# EtherCAT.net
KiCad netlist of a schematic drawn in Altium Designer
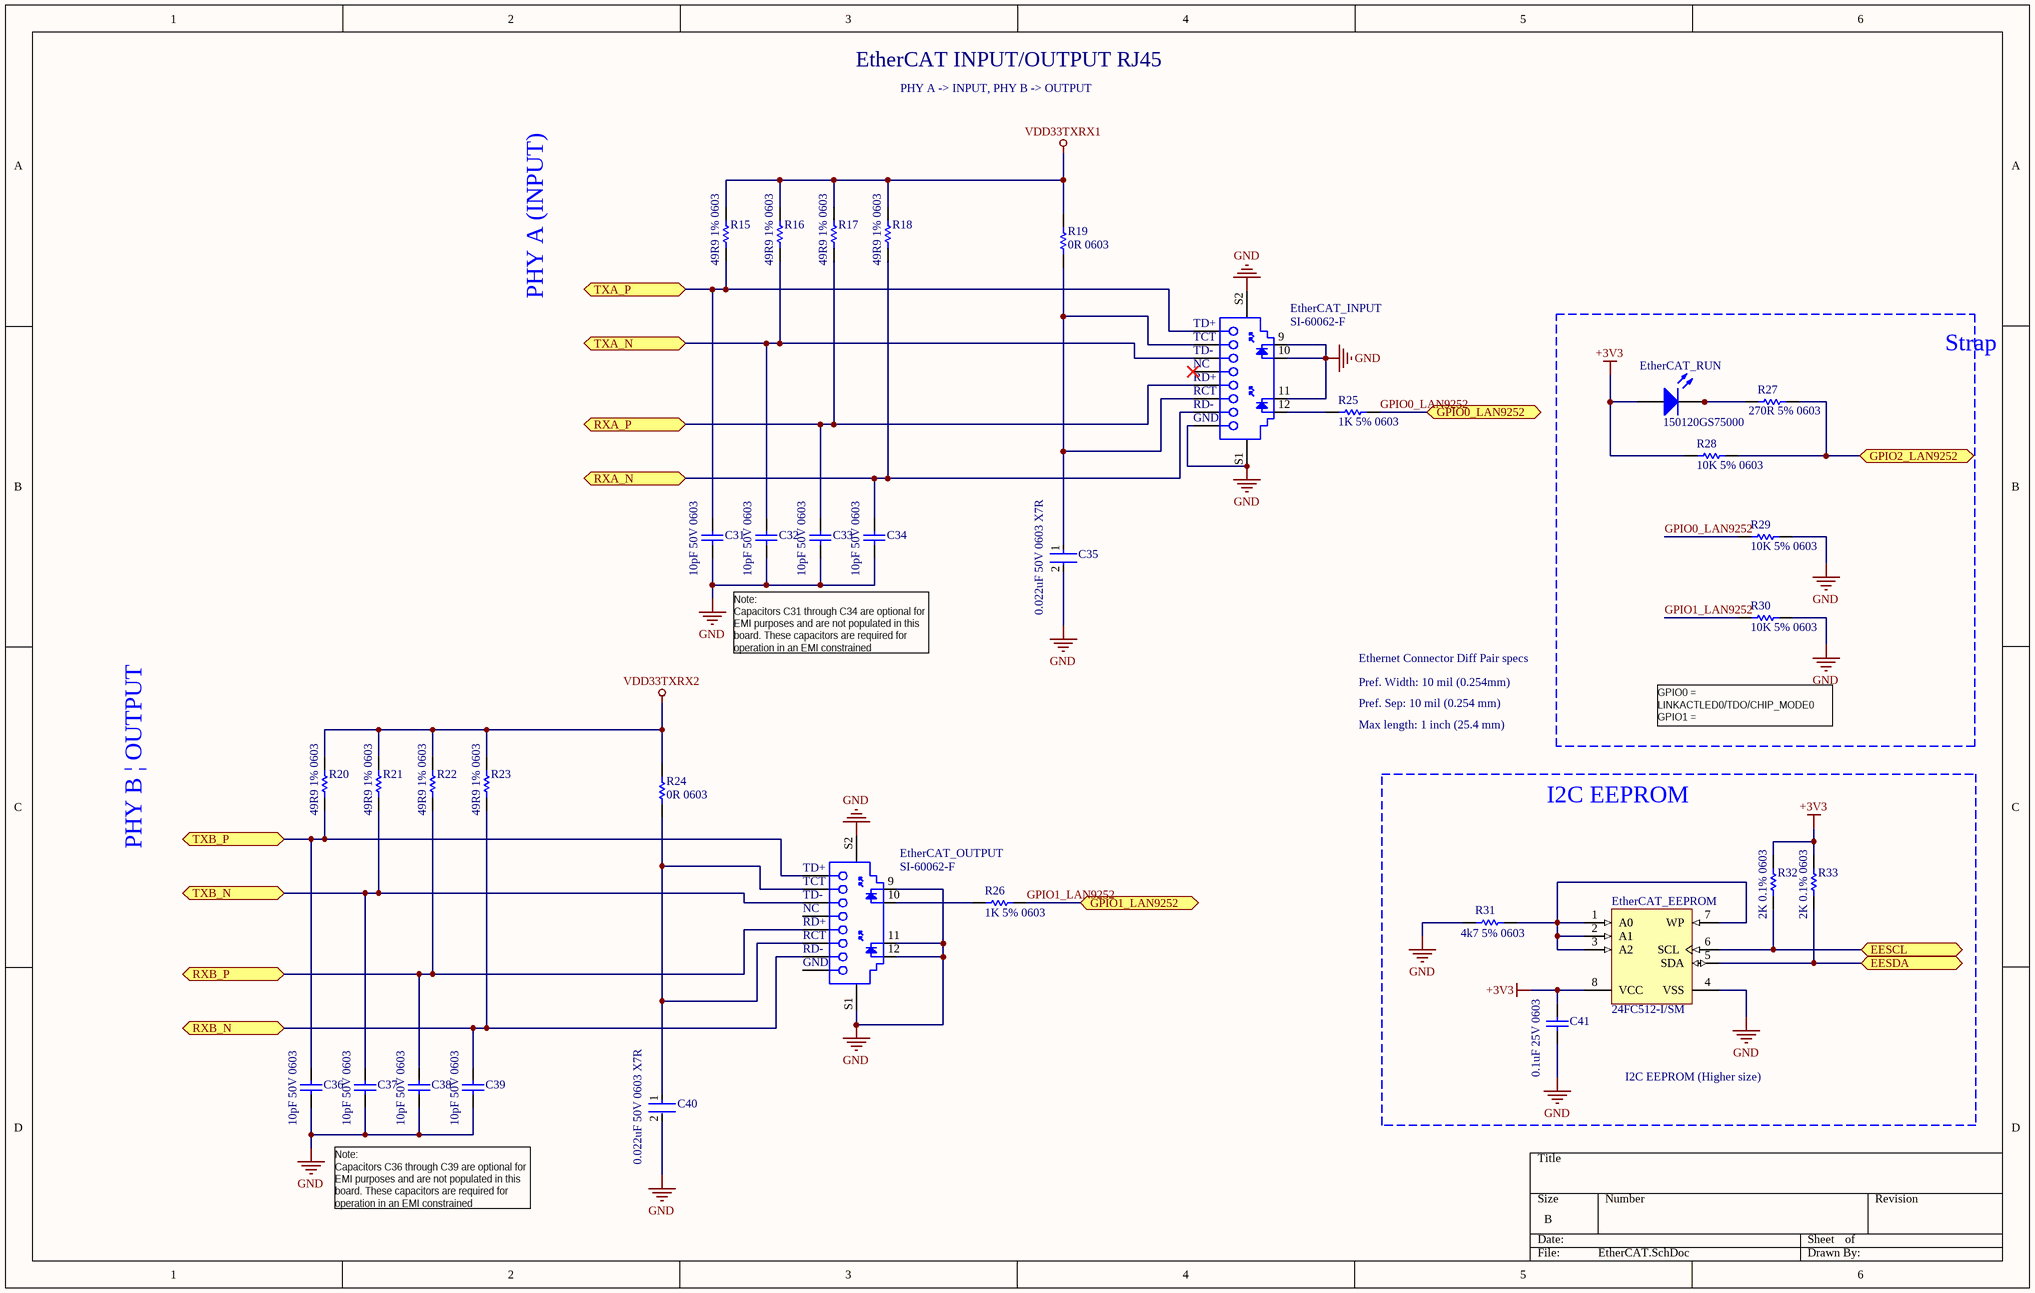
[diagram p0: EtherCAT.SchDoc]

(export (version "E")
  (design (tool "Eeschema 10.0.6"))
  (components
    (comp (ref "C31")
      (value "10pF 50V 0603")
      (footprint "CAPC1608X90X35LL10T15")
      (fields (field (name "PART NUMBER") "GRM1885C1H100JA01D") (field (name "MANUFACTURER") "Murata"))
      (libsource (lib "Altium Content Vault") (part "CAP"))
    )
    (comp (ref "C32")
      (value "10pF 50V 0603")
      (footprint "CAPC1608X90X35LL10T15")
      (fields (field (name "PART NUMBER") "GRM1885C1H100JA01D") (field (name "MANUFACTURER") "Murata"))
      (libsource (lib "Altium Content Vault") (part "CAP"))
    )
    (comp (ref "C33")
      (value "10pF 50V 0603")
      (footprint "CAPC1608X90X35LL10T15")
      (fields (field (name "PART NUMBER") "GRM1885C1H100JA01D") (field (name "MANUFACTURER") "Murata"))
      (libsource (lib "Altium Content Vault") (part "CAP"))
    )
    (comp (ref "C34")
      (value "10pF 50V 0603")
      (footprint "CAPC1608X90X35LL10T15")
      (fields (field (name "PART NUMBER") "GRM1885C1H100JA01D") (field (name "MANUFACTURER") "Murata"))
      (libsource (lib "Altium Content Vault") (part "CAP"))
    )
    (comp (ref "C35")
      (value "0.022uF 50V 0603 X7R")
      (footprint "FP-C0603C-CF-MFG")
      (description "Ceramic Capacitor 0.022Uf 50V, X7R, 10%, 0603, Full Reel")
      (fields
        (field (name "OCTOPART") "https://octopart.com/c0603c223k5ractu-kemet-97352")
        (field (name "MANUFACTURER PART NUMBER") "C0603C223K5RACTU")
      )
      (libsource (lib "Altium Content Vault") (part "b4654b650e69147ec39a6b967a45e02"))
    )
    (comp (ref "C36")
      (value "10pF 50V 0603")
      (footprint "CAPC1608X90X35LL10T15")
      (fields (field (name "PART NUMBER") "GRM1885C1H100JA01D") (field (name "MANUFACTURER") "Murata"))
      (libsource (lib "Altium Content Vault") (part "CAP"))
    )
    (comp (ref "C37")
      (value "10pF 50V 0603")
      (footprint "CAPC1608X90X35LL10T15")
      (fields (field (name "PART NUMBER") "GRM1885C1H100JA01D") (field (name "MANUFACTURER") "Murata"))
      (libsource (lib "Altium Content Vault") (part "CAP"))
    )
    (comp (ref "C38")
      (value "10pF 50V 0603")
      (footprint "CAPC1608X90X35LL10T15")
      (fields (field (name "PART NUMBER") "GRM1885C1H100JA01D") (field (name "MANUFACTURER") "Murata"))
      (libsource (lib "Altium Content Vault") (part "CAP"))
    )
    (comp (ref "C39")
      (value "10pF 50V 0603")
      (footprint "CAPC1608X90X35LL10T15")
      (fields (field (name "PART NUMBER") "GRM1885C1H100JA01D") (field (name "MANUFACTURER") "Murata"))
      (libsource (lib "Altium Content Vault") (part "CAP"))
    )
    (comp (ref "C40")
      (value "0.022uF 50V 0603 X7R")
      (footprint "FP-C0603C-CF-MFG")
      (description "Ceramic Capacitor 0.022Uf 50V, X7R, 10%, 0603, Full Reel")
      (fields
        (field (name "OCTOPART") "https://octopart.com/c0603c223k5ractu-kemet-97352")
        (field (name "MANUFACTURER PART NUMBER") "C0603C223K5RACTU")
      )
      (libsource (lib "Altium Content Vault") (part "b4654b650e69147ec39a6b967a45e02"))
    )
    (comp (ref "C41")
      (value "0.1uF 25V 0603")
      (footprint "CAPC1608X90X35LL10T15")
      (fields (field (name "PART NUMBER") "GRM188R71E104KA01D") (field (name "MANUFACTURER") "Murata"))
      (libsource (lib "Altium Content Vault") (part "CAP"))
    )
    (comp (ref "EtherCAT_EEPROM")
      (value "24FC512-I/SM")
      (footprint "SOIJ-SM8_M")
      (description "512Kbit, 1MHz, 2.5V, I2C Serial EEPROM, 8-Pin SOIC 208mil, Industrial Temperature")
      (libsource (lib "Altium Content Vault") (part "MEM-SEEPROM-34AA02-IL8"))
    )
    (comp (ref "EtherCAT_INPUT")
      (value "SI-60062-F")
      (footprint "BELF-SI-60062-F_V")
      (description "1 Port RJ45 Magjack Connector with Yellow and Green LED, 10/100 Base-T, 12-Pin THD, RoHS, Tray")
      (fields (field (name "MANUFACTURER") "Bel Fuse"))
      (libsource (lib "Altium Content Vault") (part "RJ45-12-2SHLD"))
    )
    (comp (ref "EtherCAT_OUTPUT")
      (value "SI-60062-F")
      (footprint "BELF-SI-60062-F_V")
      (description "1 Port RJ45 Magjack Connector with Yellow and Green LED, 10/100 Base-T, 12-Pin THD, RoHS, Tray")
      (fields (field (name "MANUFACTURER") "Bel Fuse"))
      (libsource (lib "Altium Content Vault") (part "RJ45-12-2SHLD"))
    )
    (comp (ref "EtherCAT_RUN")
      (value "150120GS75000")
      (footprint "1206_A")
      (description "SMD mono-color Chip LED, WL-SMCW, Green")
      (fields (field (name "MANUFACTURER") "Wuerth Elektronik"))
      (libsource (lib "Altium Content Vault") (part "WE-LED_K1A2-2"))
    )
    (comp (ref "R15")
      (value "49R9 1% 0603")
      (footprint "RESC1608X55X25NL10T15")
      (libsource (lib "Altium Content Vault") (part "RES-2"))
    )
    (comp (ref "R16")
      (value "49R9 1% 0603")
      (footprint "RESC1608X55X25NL10T15")
      (libsource (lib "Altium Content Vault") (part "RES-2"))
    )
    (comp (ref "R17")
      (value "49R9 1% 0603")
      (footprint "RESC1608X55X25NL10T15")
      (libsource (lib "Altium Content Vault") (part "RES-2"))
    )
    (comp (ref "R18")
      (value "49R9 1% 0603")
      (footprint "RESC1608X55X25NL10T15")
      (libsource (lib "Altium Content Vault") (part "RES-2"))
    )
    (comp (ref "R19")
      (value "0R 0603")
      (footprint "RESC1608X55X25ML10T15")
      (description "Chip Resistor, 0 Ohm, +/- 5%, 0.1 W, -55 to 155 degC, 0603 (1608 Metric), RoHS, Tape and Reel")
      (fields (field (name "TOLERANCE") "5%") (field (name "MANUFACTURER") "Yageo"))
      (libsource (lib "Altium Content Vault") (part "RES-2"))
    )
    (comp (ref "R20")
      (value "49R9 1% 0603")
      (footprint "RESC1608X55X25NL10T15")
      (libsource (lib "Altium Content Vault") (part "RES-2"))
    )
    (comp (ref "R21")
      (value "49R9 1% 0603")
      (footprint "RESC1608X55X25NL10T15")
      (libsource (lib "Altium Content Vault") (part "RES-2"))
    )
    (comp (ref "R22")
      (value "49R9 1% 0603")
      (footprint "RESC1608X55X25NL10T15")
      (libsource (lib "Altium Content Vault") (part "RES-2"))
    )
    (comp (ref "R23")
      (value "49R9 1% 0603")
      (footprint "RESC1608X55X25NL10T15")
      (libsource (lib "Altium Content Vault") (part "RES-2"))
    )
    (comp (ref "R24")
      (value "0R 0603")
      (footprint "RESC1608X55X25ML10T15")
      (description "Chip Resistor, 0 Ohm, +/- 5%, 0.1 W, -55 to 155 degC, 0603 (1608 Metric), RoHS, Tape and Reel")
      (fields (field (name "TOLERANCE") "5%") (field (name "MANUFACTURER") "Yageo"))
      (libsource (lib "Altium Content Vault") (part "RES-2"))
    )
    (comp (ref "R25")
      (value "1K 5% 0603")
      (footprint "RESC1608X55X25NL10T15")
      (description "Chip Resistor, 1 KOhm, +/-1%, 0.1 W, -55 to 155 degC, 0603 (1608 Metric), RoHS, Tape and Reel")
      (fields (field (name "MANUFACTURER") "Yageo"))
      (libsource (lib "Altium Content Vault") (part "RES-2"))
    )
    (comp (ref "R26")
      (value "1K 5% 0603")
      (footprint "RESC1608X55X25NL10T15")
      (description "Chip Resistor, 1 KOhm, +/-1%, 0.1 W, -55 to 155 degC, 0603 (1608 Metric), RoHS, Tape and Reel")
      (fields (field (name "MANUFACTURER") "Yageo"))
      (libsource (lib "Altium Content Vault") (part "RES-2"))
    )
    (comp (ref "R27")
      (value "270R 5% 0603")
      (footprint "RESC1608X55X25LL10T15")
      (description "Chip Resistor, 270 Ohm, +/- 5%, 0.1 W, -55 to 155 degC, 0603 (1608 Metric), RoHS, Tape and Reel")
      (fields (field (name "MANUFACTURER") "Yageo"))
      (libsource (lib "Altium Content Vault") (part "RES-2"))
    )
    (comp (ref "R28")
      (value "10K 5% 0603")
      (footprint "RESC1608X55X25ML10T15")
      (description "Chip Resistor, 10 KOhm, +/- 1%, 01 W, -55 to 155 degC, 0603 (1608 Metric), RoHS, Tape and Reel")
      (fields (field (name "MANUFACTURER") "Yageo") (field (name "TOLERANCE") "1%"))
      (libsource (lib "Altium Content Vault") (part "RES-2"))
    )
    (comp (ref "R29")
      (value "10K 5% 0603")
      (footprint "RESC1608X55X25ML10T15")
      (description "Chip Resistor, 10 KOhm, +/- 1%, 01 W, -55 to 155 degC, 0603 (1608 Metric), RoHS, Tape and Reel")
      (fields (field (name "MANUFACTURER") "Yageo") (field (name "TOLERANCE") "1%"))
      (libsource (lib "Altium Content Vault") (part "RES-2"))
    )
    (comp (ref "R30")
      (value "10K 5% 0603")
      (footprint "RESC1608X55X25ML10T15")
      (description "Chip Resistor, 10 KOhm, +/- 1%, 01 W, -55 to 155 degC, 0603 (1608 Metric), RoHS, Tape and Reel")
      (fields (field (name "MANUFACTURER") "Yageo") (field (name "TOLERANCE") "1%"))
      (libsource (lib "Altium Content Vault") (part "RES-2"))
    )
    (comp (ref "R31")
      (value "4k7 5% 0603")
      (footprint "RESC1608X55X25ML10T15")
      (description "Chip Resistor, 4.7 KOhm, +/- 5%, 100 mW, -55 to 155 degC, 0603 (1608 Metric), RoHS, Tape and Reel")
      (fields (field (name "TOLERANCE") "5%") (field (name "MANUFACTURER") "Yageo"))
      (libsource (lib "Altium Content Vault") (part "RES-2"))
    )
    (comp (ref "R32")
      (value "2K 0.1% 0603")
      (footprint "RESC1608X55X25ML10T15")
      (fields (field (name "PART NUMBER") "RT0603BRD072KL") (field (name "MANUFACTURER") "Yageo"))
      (libsource (lib "Altium Content Vault") (part "RES"))
    )
    (comp (ref "R33")
      (value "2K 0.1% 0603")
      (footprint "RESC1608X55X25ML10T15")
      (fields (field (name "PART NUMBER") "RT0603BRD072KL") (field (name "MANUFACTURER") "Yageo"))
      (libsource (lib "Altium Content Vault") (part "RES"))
    )
  )
  (nets
    (net (code "1") (name "+3V3") (class "Default")
      (node (ref "C41") (pin "2") (pinfunction "2_2") (pintype "passive"))
      (node (ref "EtherCAT_EEPROM") (pin "8") (pinfunction "VCC_8") (pintype "power_in"))
      (node (ref "EtherCAT_RUN") (pin "2") (pinfunction "A_2") (pintype "passive"))
      (node (ref "R28") (pin "2") (pinfunction "2_2") (pintype "passive"))
      (node (ref "R32") (pin "2") (pinfunction "2_2") (pintype "passive"))
      (node (ref "R33") (pin "2") (pinfunction "2_2") (pintype "passive"))
    )
    (net (code "2") (name "/EESCL") (class "Default")
      (node (ref "EtherCAT_EEPROM") (pin "6") (pinfunction "SCL_6") (pintype "input"))
      (node (ref "R32") (pin "1") (pinfunction "1_1") (pintype "passive"))
    )
    (net (code "3") (name "/EESDA") (class "Default")
      (node (ref "EtherCAT_EEPROM") (pin "5") (pinfunction "SDA_5") (pintype "bidirectional"))
      (node (ref "R33") (pin "1") (pinfunction "1_1") (pintype "passive"))
    )
    (net (code "4") (name "/GPIO0_LAN9252") (class "Default")
      (node (ref "R25") (pin "2") (pinfunction "2_2") (pintype "passive"))
      (node (ref "R29") (pin "2") (pinfunction "2_2") (pintype "passive"))
    )
    (net (code "5") (name "/GPIO1_LAN9252") (class "Default")
      (node (ref "R26") (pin "2") (pinfunction "2_2") (pintype "passive"))
      (node (ref "R30") (pin "2") (pinfunction "2_2") (pintype "passive"))
    )
    (net (code "6") (name "/GPIO2_LAN9252") (class "Default")
      (node (ref "R27") (pin "2") (pinfunction "2_2") (pintype "passive"))
      (node (ref "R28") (pin "1") (pinfunction "1_1") (pintype "passive"))
    )
    (net (code "7") (name "/RXA_N") (class "Default")
      (node (ref "C34") (pin "2") (pinfunction "2_2") (pintype "passive"))
      (node (ref "EtherCAT_INPUT") (pin "7") (pinfunction "RD-_7") (pintype "passive"))
      (node (ref "R18") (pin "1") (pinfunction "1_1") (pintype "passive"))
    )
    (net (code "8") (name "/RXA_P") (class "Default")
      (node (ref "C33") (pin "2") (pinfunction "2_2") (pintype "passive"))
      (node (ref "EtherCAT_INPUT") (pin "5") (pinfunction "RD+_5") (pintype "passive"))
      (node (ref "R17") (pin "1") (pinfunction "1_1") (pintype "passive"))
    )
    (net (code "9") (name "/RXB_N") (class "Default")
      (node (ref "C39") (pin "2") (pinfunction "2_2") (pintype "passive"))
      (node (ref "EtherCAT_OUTPUT") (pin "7") (pinfunction "RD-_7") (pintype "passive"))
      (node (ref "R23") (pin "1") (pinfunction "1_1") (pintype "passive"))
    )
    (net (code "10") (name "/RXB_P") (class "Default")
      (node (ref "C38") (pin "2") (pinfunction "2_2") (pintype "passive"))
      (node (ref "EtherCAT_OUTPUT") (pin "5") (pinfunction "RD+_5") (pintype "passive"))
      (node (ref "R22") (pin "1") (pinfunction "1_1") (pintype "passive"))
    )
    (net (code "11") (name "/TXA_N") (class "Default")
      (node (ref "C32") (pin "2") (pinfunction "2_2") (pintype "passive"))
      (node (ref "EtherCAT_INPUT") (pin "3") (pinfunction "TD-_3") (pintype "passive"))
      (node (ref "R16") (pin "1") (pinfunction "1_1") (pintype "passive"))
    )
    (net (code "12") (name "/TXA_P") (class "Default")
      (node (ref "C31") (pin "2") (pinfunction "2_2") (pintype "passive"))
      (node (ref "EtherCAT_INPUT") (pin "1") (pinfunction "TD+_1") (pintype "passive"))
      (node (ref "R15") (pin "1") (pinfunction "1_1") (pintype "passive"))
    )
    (net (code "13") (name "/TXB_N") (class "Default")
      (node (ref "C37") (pin "2") (pinfunction "2_2") (pintype "passive"))
      (node (ref "EtherCAT_OUTPUT") (pin "3") (pinfunction "TD-_3") (pintype "passive"))
      (node (ref "R21") (pin "1") (pinfunction "1_1") (pintype "passive"))
    )
    (net (code "14") (name "/TXB_P") (class "Default")
      (node (ref "C36") (pin "2") (pinfunction "2_2") (pintype "passive"))
      (node (ref "EtherCAT_OUTPUT") (pin "1") (pinfunction "TD+_1") (pintype "passive"))
      (node (ref "R20") (pin "1") (pinfunction "1_1") (pintype "passive"))
    )
    (net (code "15") (name "GND") (class "Default")
      (node (ref "C31") (pin "1") (pinfunction "1_1") (pintype "passive"))
      (node (ref "C32") (pin "1") (pinfunction "1_1") (pintype "passive"))
      (node (ref "C33") (pin "1") (pinfunction "1_1") (pintype "passive"))
      (node (ref "C34") (pin "1") (pinfunction "1_1") (pintype "passive"))
      (node (ref "C35") (pin "2") (pinfunction "2_2") (pintype "passive"))
      (node (ref "C36") (pin "1") (pinfunction "1_1") (pintype "passive"))
      (node (ref "C37") (pin "1") (pinfunction "1_1") (pintype "passive"))
      (node (ref "C38") (pin "1") (pinfunction "1_1") (pintype "passive"))
      (node (ref "C39") (pin "1") (pinfunction "1_1") (pintype "passive"))
      (node (ref "C40") (pin "2") (pinfunction "2_2") (pintype "passive"))
      (node (ref "C41") (pin "1") (pinfunction "1_1") (pintype "passive"))
      (node (ref "EtherCAT_EEPROM") (pin "4") (pinfunction "VSS_4") (pintype "power_in"))
      (node (ref "EtherCAT_INPUT") (pin "10") (pinfunction "10_10") (pintype "passive"))
      (node (ref "EtherCAT_INPUT") (pin "11") (pinfunction "11_11") (pintype "passive"))
      (node (ref "EtherCAT_INPUT") (pin "8") (pinfunction "GND_8") (pintype "passive"))
      (node (ref "EtherCAT_INPUT") (pin "9") (pinfunction "9_9") (pintype "passive"))
      (node (ref "EtherCAT_INPUT") (pin "S1") (pinfunction "S1_S1") (pintype "passive"))
      (node (ref "EtherCAT_INPUT") (pin "S2") (pinfunction "S2_S2") (pintype "passive"))
      (node (ref "EtherCAT_OUTPUT") (pin "11") (pinfunction "11_11") (pintype "passive"))
      (node (ref "EtherCAT_OUTPUT") (pin "12") (pinfunction "12_12") (pintype "passive"))
      (node (ref "EtherCAT_OUTPUT") (pin "9") (pinfunction "9_9") (pintype "passive"))
      (node (ref "EtherCAT_OUTPUT") (pin "S1") (pinfunction "S1_S1") (pintype "passive"))
      (node (ref "EtherCAT_OUTPUT") (pin "S2") (pinfunction "S2_S2") (pintype "passive"))
      (node (ref "R29") (pin "1") (pinfunction "1_1") (pintype "passive"))
      (node (ref "R30") (pin "1") (pinfunction "1_1") (pintype "passive"))
      (node (ref "R31") (pin "1") (pinfunction "1_1") (pintype "passive"))
    )
    (net (code "16") (name "Net-(EtherCAT_EEPROM-A0)") (class "Default")
      (node (ref "EtherCAT_EEPROM") (pin "1") (pinfunction "A0_1") (pintype "input"))
      (node (ref "EtherCAT_EEPROM") (pin "2") (pinfunction "A1_2") (pintype "input"))
      (node (ref "EtherCAT_EEPROM") (pin "3") (pinfunction "A2_3") (pintype "input"))
      (node (ref "EtherCAT_EEPROM") (pin "7") (pinfunction "WP_7") (pintype "input"))
      (node (ref "R31") (pin "2") (pinfunction "2_2") (pintype "passive"))
    )
    (net (code "17") (name "Net-(EtherCAT_INPUT-Pad12)") (class "Default")
      (node (ref "EtherCAT_INPUT") (pin "12") (pinfunction "12_12") (pintype "passive"))
      (node (ref "R25") (pin "1") (pinfunction "1_1") (pintype "passive"))
    )
    (net (code "18") (name "Net-(EtherCAT_INPUT-RCT)") (class "Default")
      (node (ref "C35") (pin "1") (pinfunction "1_1") (pintype "passive"))
      (node (ref "EtherCAT_INPUT") (pin "2") (pinfunction "TCT_2") (pintype "passive"))
      (node (ref "EtherCAT_INPUT") (pin "6") (pinfunction "RCT_6") (pintype "passive"))
      (node (ref "R19") (pin "1") (pinfunction "1_1") (pintype "passive"))
    )
    (net (code "19") (name "Net-(EtherCAT_OUTPUT-Pad10)") (class "Default")
      (node (ref "EtherCAT_OUTPUT") (pin "10") (pinfunction "10_10") (pintype "passive"))
      (node (ref "R26") (pin "1") (pinfunction "1_1") (pintype "passive"))
    )
    (net (code "20") (name "Net-(EtherCAT_OUTPUT-RCT)") (class "Default")
      (node (ref "C40") (pin "1") (pinfunction "1_1") (pintype "passive"))
      (node (ref "EtherCAT_OUTPUT") (pin "2") (pinfunction "TCT_2") (pintype "passive"))
      (node (ref "EtherCAT_OUTPUT") (pin "6") (pinfunction "RCT_6") (pintype "passive"))
      (node (ref "R24") (pin "1") (pinfunction "1_1") (pintype "passive"))
    )
    (net (code "21") (name "Net-(EtherCAT_RUN-K)") (class "Default")
      (node (ref "EtherCAT_RUN") (pin "1") (pinfunction "K_1") (pintype "passive"))
      (node (ref "R27") (pin "1") (pinfunction "1_1") (pintype "passive"))
    )
    (net (code "22") (name "VDD33TXRX1") (class "Default")
      (node (ref "R15") (pin "2") (pinfunction "2_2") (pintype "passive"))
      (node (ref "R16") (pin "2") (pinfunction "2_2") (pintype "passive"))
      (node (ref "R17") (pin "2") (pinfunction "2_2") (pintype "passive"))
      (node (ref "R18") (pin "2") (pinfunction "2_2") (pintype "passive"))
      (node (ref "R19") (pin "2") (pinfunction "2_2") (pintype "passive"))
    )
    (net (code "23") (name "VDD33TXRX2") (class "Default")
      (node (ref "R20") (pin "2") (pinfunction "2_2") (pintype "passive"))
      (node (ref "R21") (pin "2") (pinfunction "2_2") (pintype "passive"))
      (node (ref "R22") (pin "2") (pinfunction "2_2") (pintype "passive"))
      (node (ref "R23") (pin "2") (pinfunction "2_2") (pintype "passive"))
      (node (ref "R24") (pin "2") (pinfunction "2_2") (pintype "passive"))
    )
    (net (code "24") (name "unconnected-(EtherCAT_INPUT-NC-Pad4)") (class "Default")
      (node (ref "EtherCAT_INPUT") (pin "4") (pinfunction "NC_4") (pintype "passive+no_connect"))
    )
    (net (code "25") (name "unconnected-(EtherCAT_OUTPUT-GND-Pad8)") (class "Default")
      (node (ref "EtherCAT_OUTPUT") (pin "8") (pinfunction "GND_8") (pintype "passive"))
    )
    (net (code "26") (name "unconnected-(EtherCAT_OUTPUT-NC-Pad4)") (class "Default")
      (node (ref "EtherCAT_OUTPUT") (pin "4") (pinfunction "NC_4") (pintype "passive"))
    )
  )
)
